# dac-converter.net
KiCad netlist of a schematic drawn in Altium Designer
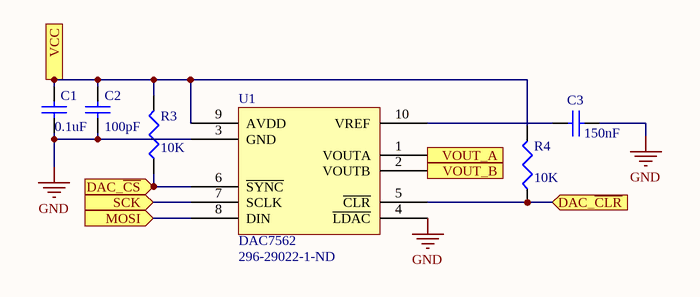
[diagram p0: dac-converter.SchDoc]

(export (version "E")
  (design (tool "Eeschema 10.0.6"))
  (components
    (comp (ref "C1")
      (value "0.1uF")
      (footprint "0402")
      (description "Capacitor (Semiconductor SIM Model)")
      (fields (field (name "PUBLISHER") "Altium Limited"))
      (libsource (lib "Miscellaneous Devices") (part "Cap Semi"))
    )
    (comp (ref "C2")
      (value "100pF")
      (footprint "0402")
      (description "Capacitor (Semiconductor SIM Model)")
      (fields (field (name "PUBLISHER") "Altium Limited"))
      (libsource (lib "Miscellaneous Devices") (part "Cap Semi"))
    )
    (comp (ref "C3")
      (value "150nF")
      (footprint "0402")
      (description "Capacitor (Semiconductor SIM Model)")
      (fields (field (name "PUBLISHER") "Altium Limited"))
      (libsource (lib "Miscellaneous Devices") (part "Cap Semi"))
    )
    (comp (ref "R3")
      (value "10K")
      (footprint "0402")
      (description "Resistor")
      (fields (field (name "PUBLISHER") "Altium Limited"))
      (libsource (lib "Miscellaneous Devices") (part "Res3"))
    )
    (comp (ref "R4")
      (value "10K")
      (footprint "0402")
      (description "Resistor")
      (fields (field (name "PUBLISHER") "Altium Limited"))
      (libsource (lib "Miscellaneous Devices") (part "Res3"))
    )
    (comp (ref "U1")
      (value "DAC7562")
      (footprint "SOP10-50P300X300-10N")
      (description "12-bit, low-power, voltage-output DAC with internal reference.")
      (fields (field (name "SUPPLIER PART NUMBER 1") "296-29022-1-ND"))
      (libsource (lib "PAY") (part "DAC7562"))
    )
  )
  (nets
    (net (code "1") (name "/DAC_~{CLR}") (class "Default")
      (node (ref "R4") (pin "1") (pinfunction "1_1") (pintype "passive"))
      (node (ref "U1") (pin "5") (pinfunction "~{CLR}_5") (pintype "passive"))
    )
    (net (code "2") (name "/DAC_~{CS}") (class "Default")
      (node (ref "R3") (pin "1") (pinfunction "1_1") (pintype "passive"))
      (node (ref "U1") (pin "6") (pinfunction "~{SYNC}_6") (pintype "passive"))
    )
    (net (code "3") (name "/MOSI") (class "Default")
      (node (ref "U1") (pin "8") (pinfunction "DIN_8") (pintype "passive"))
    )
    (net (code "4") (name "/SCK") (class "Default")
      (node (ref "U1") (pin "7") (pinfunction "SCLK_7") (pintype "passive"))
    )
    (net (code "5") (name "/VCC") (class "Default")
      (node (ref "C1") (pin "2") (pinfunction "2_2") (pintype "passive"))
      (node (ref "C2") (pin "2") (pinfunction "2_2") (pintype "passive"))
      (node (ref "R3") (pin "2") (pinfunction "2_2") (pintype "passive"))
      (node (ref "R4") (pin "2") (pinfunction "2_2") (pintype "passive"))
      (node (ref "U1") (pin "9") (pinfunction "AVDD_9") (pintype "passive"))
    )
    (net (code "6") (name "/VOUT_A") (class "Default")
      (node (ref "U1") (pin "1") (pinfunction "VOUTA_1") (pintype "passive"))
    )
    (net (code "7") (name "/VOUT_B") (class "Default")
      (node (ref "U1") (pin "2") (pinfunction "VOUTB_2") (pintype "passive"))
    )
    (net (code "8") (name "GND") (class "Default")
      (node (ref "C1") (pin "1") (pinfunction "1_1") (pintype "passive"))
      (node (ref "C2") (pin "1") (pinfunction "1_1") (pintype "passive"))
      (node (ref "C3") (pin "2") (pinfunction "2_2") (pintype "passive"))
      (node (ref "U1") (pin "3") (pinfunction "GND_3") (pintype "passive"))
      (node (ref "U1") (pin "4") (pinfunction "~{LDAC}_4") (pintype "passive"))
    )
    (net (code "9") (name "Net-(U1-VREF)") (class "Default")
      (node (ref "C3") (pin "1") (pinfunction "1_1") (pintype "passive"))
      (node (ref "U1") (pin "10") (pinfunction "VREF_10") (pintype "passive"))
    )
  )
)
